# TamaCollar1_Mk1__V45.net
KiCad netlist of a schematic drawn in EAGLE
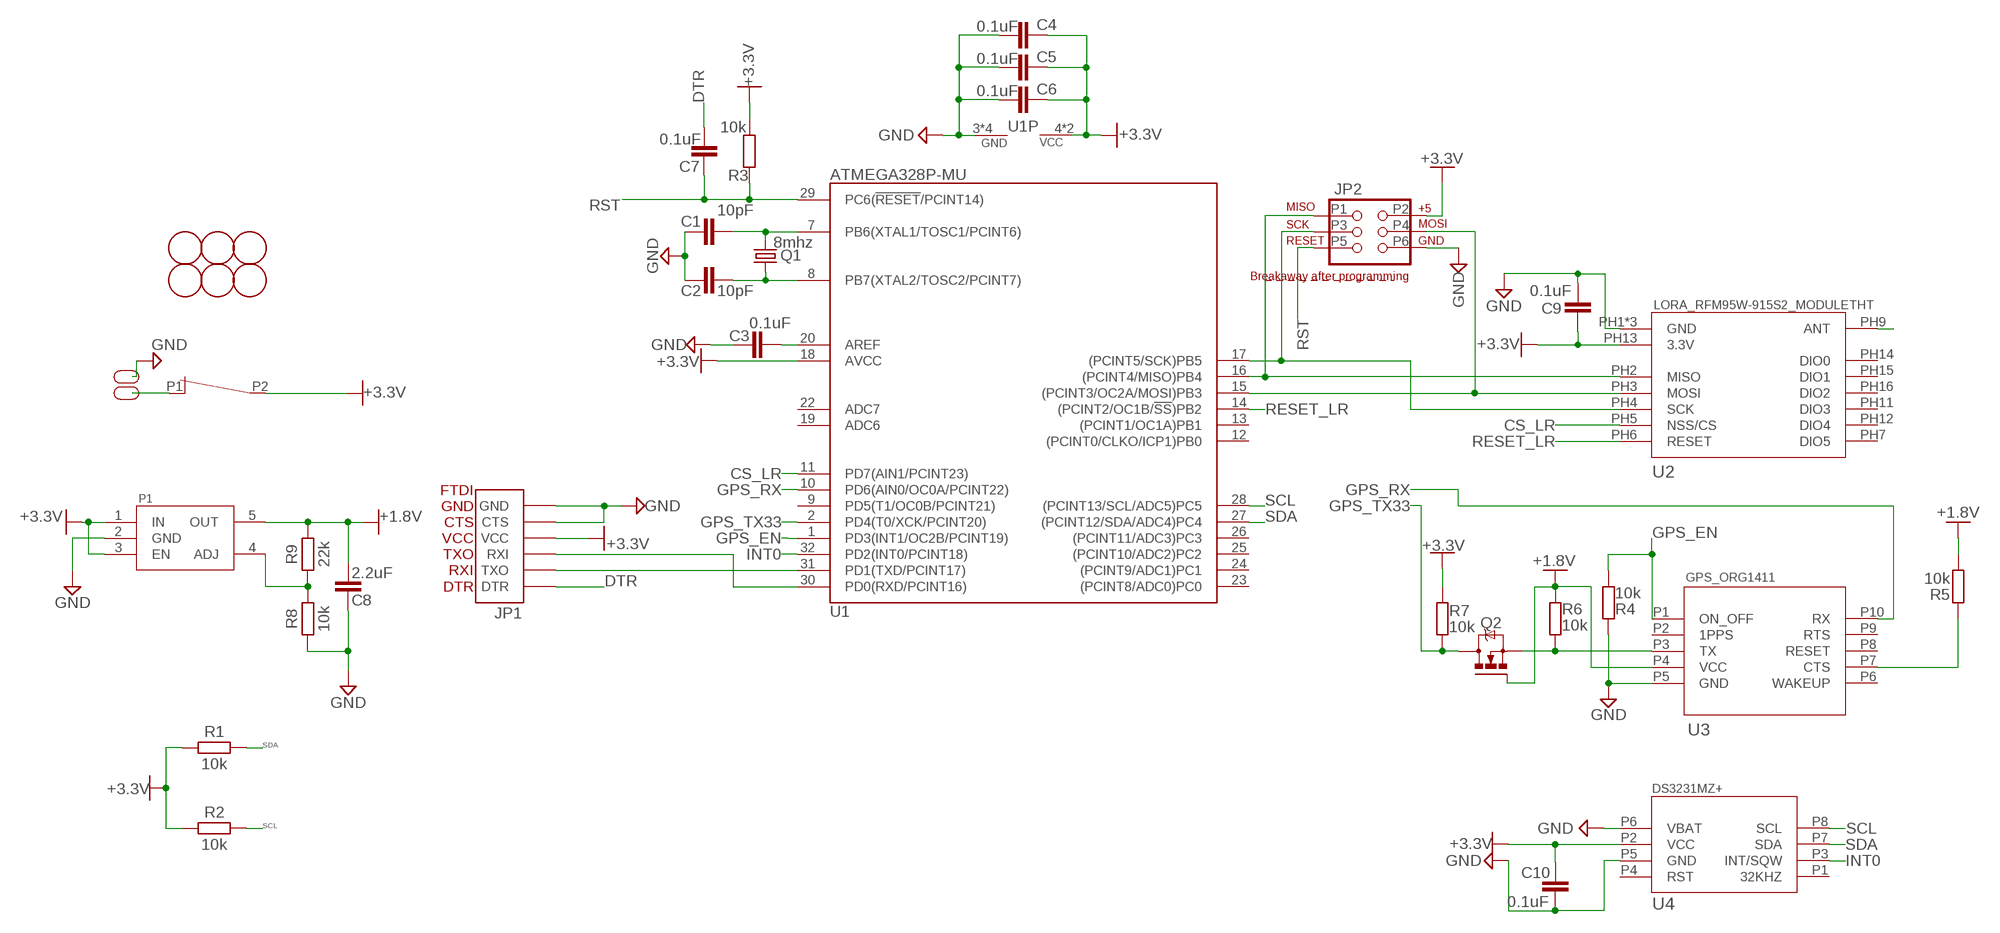
[diagram p0: schematic, sheet 1]

(export (version "E")
  (design (tool "Eeschema 10.0.6"))
  (components
    (comp (ref "BATT+")
      (value "BREAKOUT_PADL")
      (footprint "eagle-import:BREAKOUT_PAD_1_1X2MM")
      (libsource (lib "eagle-import") (part "BREAKOUT_PADL"))
    )
    (comp (ref "BR2")
      (value "MOUSEBITE3X1.25")
      (footprint "eagle-import:MOUSEBITE_3H_6TRACE(1.25MM)")
      (libsource (lib "eagle-import") (part "MOUSEBITE3X1.25"))
    )
    (comp (ref "C1")
      (value "10pF")
      (footprint "eagle-import:CAPC1005X60")
      (libsource (lib "eagle-import") (part "CCHIP-0402(1005-METRIC)_"))
    )
    (comp (ref "C2")
      (value "10pF")
      (footprint "eagle-import:CAPC1005X60")
      (libsource (lib "eagle-import") (part "CCHIP-0402(1005-METRIC)_"))
    )
    (comp (ref "C3")
      (value "0.1uF")
      (footprint "eagle-import:CAPC1005X60")
      (libsource (lib "eagle-import") (part "CCHIP-0402(1005-METRIC)_"))
    )
    (comp (ref "C4")
      (value "0.1uF")
      (footprint "eagle-import:CAPC1005X60")
      (libsource (lib "eagle-import") (part "CCHIP-0402(1005-METRIC)_"))
    )
    (comp (ref "C5")
      (value "0.1uF")
      (footprint "eagle-import:CAPC1005X60")
      (libsource (lib "eagle-import") (part "CCHIP-0402(1005-METRIC)_"))
    )
    (comp (ref "C6")
      (value "0.1uF")
      (footprint "eagle-import:CAPC1005X60")
      (libsource (lib "eagle-import") (part "CCHIP-0402(1005-METRIC)_"))
    )
    (comp (ref "C7")
      (value "0.1uF")
      (footprint "eagle-import:CAPC1005X60")
      (libsource (lib "eagle-import") (part "CCHIP-0402(1005-METRIC)_"))
    )
    (comp (ref "C8")
      (value "2.2uF")
      (footprint "eagle-import:CAPC1005X60")
      (libsource (lib "eagle-import") (part "CCHIP-0402(1005-METRIC)_"))
    )
    (comp (ref "C9")
      (value "0.1uF")
      (footprint "eagle-import:CAPC1005X60")
      (libsource (lib "eagle-import") (part "CCHIP-0402(1005-METRIC)_"))
    )
    (comp (ref "C10")
      (value "0.1uF")
      (footprint "eagle-import:CAPC1005X60")
      (libsource (lib "eagle-import") (part "CCHIP-0402(1005-METRIC)_"))
    )
    (comp (ref "F1")
      (value "FIDUCIAL")
      (footprint "eagle-import:FIDUCIAL_1MM")
      (libsource (lib "eagle-import") (part "FIDUCIAL"))
    )
    (comp (ref "F2")
      (value "FIDUCIAL")
      (footprint "eagle-import:FIDUCIAL_1MM")
      (libsource (lib "eagle-import") (part "FIDUCIAL"))
    )
    (comp (ref "F3")
      (value "FIDUCIAL")
      (footprint "eagle-import:FIDUCIAL_1MM")
      (libsource (lib "eagle-import") (part "FIDUCIAL"))
    )
    (comp (ref "F4")
      (value "FIDUCIAL")
      (footprint "eagle-import:FIDUCIAL_1MM")
      (libsource (lib "eagle-import") (part "FIDUCIAL"))
    )
    (comp (ref "F5")
      (value "FIDUCIAL")
      (footprint "eagle-import:FIDUCIAL_1MM")
      (libsource (lib "eagle-import") (part "FIDUCIAL"))
    )
    (comp (ref "F6")
      (value "FIDUCIAL")
      (footprint "eagle-import:FIDUCIAL_1MM")
      (libsource (lib "eagle-import") (part "FIDUCIAL"))
    )
    (comp (ref "GND")
      (value "BREAKOUT_PADL")
      (footprint "eagle-import:BREAKOUT_PAD_1_1X2MM")
      (libsource (lib "eagle-import") (part "BREAKOUT_PADL"))
    )
    (comp (ref "JP1")
      (value "FTDI_DEVICESMALL")
      (footprint "eagle-import:FTDI_DEVICE_SMD_SMALL")
      (libsource (lib "eagle-import") (part "FTDI_DEVICESMALL"))
    )
    (comp (ref "JP2")
      (value "AVR_SPI_PRG_61X6")
      (footprint "eagle-import:1X6-SMD")
      (libsource (lib "eagle-import") (part "AVR_SPI_PRG_61X6"))
    )
    (comp (ref "P1")
      (value "LDO_MIC5205YM5")
      (footprint "eagle-import:MIC5205")
      (libsource (lib "eagle-import") (part "LDO_MIC5205YM5"))
    )
    (comp (ref "Q1")
      (value "8mhz")
      (footprint "eagle-import:CRYSTAL_NX3225GD")
      (libsource (lib "eagle-import") (part "CRYSTAL"))
    )
    (comp (ref "Q2")
      (value "NMOSFET")
      (footprint "eagle-import:SOT23")
      (libsource (lib "eagle-import") (part "NMOSFETSOT23"))
    )
    (comp (ref "R1")
      (value "10k")
      (footprint "eagle-import:RESC1005X40")
      (libsource (lib "eagle-import") (part "RCHIP-0402(1005-METRIC)_"))
    )
    (comp (ref "R2")
      (value "10k")
      (footprint "eagle-import:RESC1005X40")
      (libsource (lib "eagle-import") (part "RCHIP-0402(1005-METRIC)_"))
    )
    (comp (ref "R3")
      (value "10k")
      (footprint "eagle-import:RESC1005X40")
      (libsource (lib "eagle-import") (part "RCHIP-0402(1005-METRIC)_"))
    )
    (comp (ref "R4")
      (value "10k")
      (footprint "eagle-import:RESC1005X40")
      (libsource (lib "eagle-import") (part "RCHIP-0402(1005-METRIC)_"))
    )
    (comp (ref "R5")
      (value "10k")
      (footprint "eagle-import:RESC1005X40")
      (libsource (lib "eagle-import") (part "RCHIP-0402(1005-METRIC)_"))
    )
    (comp (ref "R6")
      (value "10k")
      (footprint "eagle-import:RESC1005X40")
      (libsource (lib "eagle-import") (part "RCHIP-0402(1005-METRIC)_"))
    )
    (comp (ref "R7")
      (value "10k")
      (footprint "eagle-import:RESC1005X40")
      (libsource (lib "eagle-import") (part "RCHIP-0402(1005-METRIC)_"))
    )
    (comp (ref "R8")
      (value "10k")
      (footprint "eagle-import:RESC1005X40")
      (libsource (lib "eagle-import") (part "RCHIP-0402(1005-METRIC)_"))
    )
    (comp (ref "R9")
      (value "22k")
      (footprint "eagle-import:RESC1005X40")
      (libsource (lib "eagle-import") (part "RCHIP-0402(1005-METRIC)_"))
    )
    (comp (ref "SW1")
      (value "REED_SWITCH")
      (footprint "eagle-import:REED_CT05")
      (libsource (lib "eagle-import") (part "REED_SWITCH"))
    )
    (comp (ref "U1")
      (value "ATMEGA328P-MU")
      (footprint "eagle-import:QFN32_5X5_0.50")
      (fields
        (field (name "LINK") "https://www.rhydolabz.com/components-microcontrollers-c-172_192/atmega328pmu-smd-p-2612.html")
      )
      (libsource (lib "eagle-import") (part "ATMEGA8P-MU32"))
    )
    (comp (ref "U2")
      (value "LORA_RFM95W-915S2_MODULETHT")
      (footprint "eagle-import:LORA_RFM95W-915S2_16STANDOFFMODULE")
      (libsource (lib "eagle-import") (part "LORA_RFM95W-915S2_MODULETHT"))
    )
    (comp (ref "U3")
      (value "GPS_ORG1411")
      (footprint "eagle-import:ORG1411")
      (libsource (lib "eagle-import") (part "GPS_ORG1411"))
    )
    (comp (ref "U4")
      (value "DS3231MZ+")
      (footprint "eagle-import:DS3231MZ+_SOIC8")
      (libsource (lib "eagle-import") (part "DS3231MZ+"))
    )
  )
  (nets
    (net (code "1") (name "+1.8V") (class "Default")
      (node (ref "C8") (pin "2") (pinfunction "2_2") (pintype "passive"))
      (node (ref "P1") (pin "5") (pinfunction "OUT_5") (pintype "bidirectional"))
      (node (ref "Q2") (pin "1") (pinfunction "G_1") (pintype "passive"))
      (node (ref "R5") (pin "1") (pinfunction "1_1") (pintype "passive"))
      (node (ref "R6") (pin "2") (pinfunction "2_2") (pintype "passive"))
      (node (ref "R9") (pin "2") (pinfunction "2_2") (pintype "passive"))
      (node (ref "U3") (pin "P4") (pinfunction "VCC_P4") (pintype "power_in"))
    )
    (net (code "2") (name "+3.3V") (class "Default")
      (node (ref "C10") (pin "1") (pinfunction "1_1") (pintype "passive"))
      (node (ref "C4") (pin "1") (pinfunction "1_1") (pintype "passive"))
      (node (ref "C5") (pin "1") (pinfunction "1_1") (pintype "passive"))
      (node (ref "C6") (pin "1") (pinfunction "1_1") (pintype "passive"))
      (node (ref "C9") (pin "1") (pinfunction "1_1") (pintype "passive"))
      (node (ref "JP1") (pin "P4") (pinfunction "VCC_P4") (pintype "bidirectional"))
      (node (ref "JP2") (pin "P2") (pinfunction "2_P2") (pintype "passive"))
      (node (ref "P1") (pin "1") (pinfunction "IN_1") (pintype "bidirectional"))
      (node (ref "P1") (pin "3") (pinfunction "EN_3") (pintype "bidirectional"))
      (node (ref "R1") (pin "1") (pinfunction "1_1") (pintype "passive"))
      (node (ref "R2") (pin "1") (pinfunction "1_1") (pintype "passive"))
      (node (ref "R3") (pin "1") (pinfunction "1_1") (pintype "passive"))
      (node (ref "R7") (pin "2") (pinfunction "2_2") (pintype "passive"))
      (node (ref "SW1") (pin "P2") (pinfunction "PAD2_P2") (pintype "bidirectional"))
      (node (ref "U1") (pin "18") (pinfunction "AVCC_18") (pintype "power_in"))
      (node (ref "U1") (pin "4") (pinfunction "VCC_4") (pintype "power_in"))
      (node (ref "U1") (pin "6") (pinfunction "VCC_6") (pintype "power_in"))
      (node (ref "U2") (pin "PH13") (pinfunction "3.3V_PH13") (pintype "bidirectional"))
      (node (ref "U4") (pin "P2") (pinfunction "VCC_P2") (pintype "power_in"))
    )
    (net (code "3") (name "/CS_LR") (class "Default")
      (node (ref "U1") (pin "11") (pinfunction "PD7(AIN1/PCINT23)_11") (pintype "bidirectional"))
      (node (ref "U2") (pin "PH5") (pinfunction "NSS/CS_PH5") (pintype "bidirectional"))
    )
    (net (code "4") (name "/DTR") (class "Default")
      (node (ref "C7") (pin "2") (pinfunction "2_2") (pintype "passive"))
      (node (ref "JP1") (pin "P1") (pinfunction "DTR_P1") (pintype "bidirectional"))
    )
    (net (code "5") (name "/GPS_EN") (class "Default")
      (node (ref "R4") (pin "1") (pinfunction "1_1") (pintype "passive"))
      (node (ref "U1") (pin "1") (pinfunction "PD3(INT1/OC2B/PCINT19)_1") (pintype "bidirectional"))
      (node (ref "U3") (pin "P1") (pinfunction "ON_OFF_P1") (pintype "input"))
    )
    (net (code "6") (name "/GPS_RX") (class "Default")
      (node (ref "U1") (pin "10") (pinfunction "PD6(AIN0/OC0A/PCINT22)_10") (pintype "bidirectional"))
      (node (ref "U3") (pin "P10") (pinfunction "RX_P10") (pintype "bidirectional"))
    )
    (net (code "7") (name "/GPS_TX33") (class "Default")
      (node (ref "Q2") (pin "3") (pinfunction "D_3") (pintype "passive"))
      (node (ref "R7") (pin "1") (pinfunction "1_1") (pintype "passive"))
      (node (ref "U1") (pin "2") (pinfunction "PD4(T0/XCK/PCINT20)_2") (pintype "bidirectional"))
    )
    (net (code "8") (name "/INT0") (class "Default")
      (node (ref "U1") (pin "32") (pinfunction "PD2(INT0/PCINT18)_32") (pintype "bidirectional"))
      (node (ref "U4") (pin "P3") (pinfunction "INT/SQW_P3") (pintype "bidirectional"))
    )
    (net (code "9") (name "/RESET_LR") (class "Default")
      (node (ref "U1") (pin "14") (pinfunction "(PCINT2/OC1B/~{SS})PB2_14") (pintype "bidirectional"))
      (node (ref "U2") (pin "PH6") (pinfunction "RESET_PH6") (pintype "bidirectional"))
    )
    (net (code "10") (name "/RST") (class "Default")
      (node (ref "C7") (pin "1") (pinfunction "1_1") (pintype "passive"))
      (node (ref "JP2") (pin "P5") (pinfunction "5_P5") (pintype "passive"))
      (node (ref "R3") (pin "2") (pinfunction "2_2") (pintype "passive"))
      (node (ref "U1") (pin "29") (pinfunction "PC6(~{RESET}/PCINT14)_29") (pintype "bidirectional"))
    )
    (net (code "11") (name "/SCL") (class "Default")
      (node (ref "R2") (pin "2") (pinfunction "2_2") (pintype "passive"))
      (node (ref "U1") (pin "28") (pinfunction "(PCINT13/SCL/ADC5)PC5_28") (pintype "bidirectional"))
      (node (ref "U4") (pin "P8") (pinfunction "SCL_P8") (pintype "bidirectional"))
    )
    (net (code "12") (name "/SDA") (class "Default")
      (node (ref "R1") (pin "2") (pinfunction "2_2") (pintype "passive"))
      (node (ref "U1") (pin "27") (pinfunction "(PCINT12/SDA/ADC4)PC4_27") (pintype "bidirectional"))
      (node (ref "U4") (pin "P7") (pinfunction "SDA_P7") (pintype "bidirectional"))
    )
    (net (code "13") (name "GND") (class "Default")
      (node (ref "C1") (pin "1") (pinfunction "1_1") (pintype "passive"))
      (node (ref "C10") (pin "2") (pinfunction "2_2") (pintype "passive"))
      (node (ref "C2") (pin "1") (pinfunction "1_1") (pintype "passive"))
      (node (ref "C3") (pin "1") (pinfunction "1_1") (pintype "passive"))
      (node (ref "C4") (pin "2") (pinfunction "2_2") (pintype "passive"))
      (node (ref "C5") (pin "2") (pinfunction "2_2") (pintype "passive"))
      (node (ref "C6") (pin "2") (pinfunction "2_2") (pintype "passive"))
      (node (ref "C8") (pin "1") (pinfunction "1_1") (pintype "passive"))
      (node (ref "C9") (pin "2") (pinfunction "2_2") (pintype "passive"))
      (node (ref "GND") (pin "P$1") (pinfunction "P$1_P$1") (pintype "bidirectional"))
      (node (ref "JP1") (pin "P5") (pinfunction "CTS_P5") (pintype "bidirectional"))
      (node (ref "JP1") (pin "P6") (pinfunction "GND_P6") (pintype "bidirectional"))
      (node (ref "JP2") (pin "P6") (pinfunction "6_P6") (pintype "passive"))
      (node (ref "P1") (pin "2") (pinfunction "GND_2") (pintype "bidirectional"))
      (node (ref "R4") (pin "2") (pinfunction "2_2") (pintype "passive"))
      (node (ref "R8") (pin "1") (pinfunction "1_1") (pintype "passive"))
      (node (ref "U1") (pin "21") (pinfunction "GND_21") (pintype "power_in"))
      (node (ref "U1") (pin "3") (pinfunction "GND_3") (pintype "power_in"))
      (node (ref "U1") (pin "5") (pinfunction "GND_5") (pintype "power_in"))
      (node (ref "U1") (pin "EXP") (pinfunction "GND_EXP") (pintype "power_in"))
      (node (ref "U2") (pin "PH1") (pinfunction "GND_PH1") (pintype "bidirectional"))
      (node (ref "U2") (pin "PH10") (pinfunction "GND_PH10") (pintype "bidirectional"))
      (node (ref "U2") (pin "PH8") (pinfunction "GND_PH8") (pintype "bidirectional"))
      (node (ref "U3") (pin "P5") (pinfunction "GND_P5") (pintype "power_in"))
      (node (ref "U4") (pin "P5") (pinfunction "GND_P5") (pintype "power_in"))
      (node (ref "U4") (pin "P6") (pinfunction "VBAT_P6") (pintype "power_in"))
    )
    (net (code "14") (name "Net-(JP1-RXI)") (class "Default")
      (node (ref "JP1") (pin "P3") (pinfunction "RXI_P3") (pintype "bidirectional"))
      (node (ref "U1") (pin "30") (pinfunction "PD0(RXD/PCINT16)_30") (pintype "bidirectional"))
    )
    (net (code "15") (name "Net-(JP1-TXO)") (class "Default")
      (node (ref "JP1") (pin "P2") (pinfunction "TXO_P2") (pintype "bidirectional"))
      (node (ref "U1") (pin "31") (pinfunction "PD1(TXD/PCINT17)_31") (pintype "bidirectional"))
    )
    (net (code "16") (name "Net-(JP2-1)") (class "Default")
      (node (ref "JP2") (pin "P1") (pinfunction "1_P1") (pintype "passive"))
      (node (ref "U1") (pin "16") (pinfunction "(PCINT4/MISO)PB4_16") (pintype "bidirectional"))
      (node (ref "U2") (pin "PH2") (pinfunction "MISO_PH2") (pintype "bidirectional"))
    )
    (net (code "17") (name "Net-(JP2-3)") (class "Default")
      (node (ref "JP2") (pin "P3") (pinfunction "3_P3") (pintype "passive"))
      (node (ref "U1") (pin "17") (pinfunction "(PCINT5/SCK)PB5_17") (pintype "bidirectional"))
      (node (ref "U2") (pin "PH4") (pinfunction "SCK_PH4") (pintype "bidirectional"))
    )
    (net (code "18") (name "Net-(JP2-4)") (class "Default")
      (node (ref "JP2") (pin "P4") (pinfunction "4_P4") (pintype "passive"))
      (node (ref "U1") (pin "15") (pinfunction "(PCINT3/OC2A/MOSI)PB3_15") (pintype "bidirectional"))
      (node (ref "U2") (pin "PH3") (pinfunction "MOSI_PH3") (pintype "bidirectional"))
    )
    (net (code "19") (name "Net-(P1-ADJ)") (class "Default")
      (node (ref "P1") (pin "4") (pinfunction "ADJ_4") (pintype "bidirectional"))
      (node (ref "R8") (pin "2") (pinfunction "2_2") (pintype "passive"))
      (node (ref "R9") (pin "1") (pinfunction "1_1") (pintype "passive"))
    )
    (net (code "20") (name "Net-(Q1-1)") (class "Default")
      (node (ref "C2") (pin "2") (pinfunction "2_2") (pintype "passive"))
      (node (ref "Q1") (pin "P1") (pinfunction "1_P1") (pintype "passive"))
      (node (ref "U1") (pin "8") (pinfunction "PB7(XTAL2/TOSC2/PCINT7)_8") (pintype "bidirectional"))
    )
    (net (code "21") (name "Net-(Q1-2)") (class "Default")
      (node (ref "C1") (pin "2") (pinfunction "2_2") (pintype "passive"))
      (node (ref "Q1") (pin "P2") (pinfunction "2_P2") (pintype "passive"))
      (node (ref "U1") (pin "7") (pinfunction "PB6(XTAL1/TOSC1/PCINT6)_7") (pintype "bidirectional"))
    )
    (net (code "22") (name "Net-(Q2-S)") (class "Default")
      (node (ref "Q2") (pin "2") (pinfunction "S_2") (pintype "passive"))
      (node (ref "R6") (pin "1") (pinfunction "1_1") (pintype "passive"))
      (node (ref "U3") (pin "P3") (pinfunction "TX_P3") (pintype "bidirectional"))
    )
    (net (code "23") (name "Net-(SW1-PAD1)") (class "Default")
      (node (ref "BATT+") (pin "P$1") (pinfunction "P$1_P$1") (pintype "bidirectional"))
      (node (ref "SW1") (pin "P1") (pinfunction "PAD1_P1") (pintype "bidirectional"))
    )
    (net (code "24") (name "Net-(U1A-AREF)") (class "Default")
      (node (ref "C3") (pin "2") (pinfunction "2_2") (pintype "passive"))
      (node (ref "U1") (pin "20") (pinfunction "AREF_20") (pintype "passive"))
    )
    (net (code "25") (name "Net-(U3-CTS)") (class "Default")
      (node (ref "R5") (pin "2") (pinfunction "2_2") (pintype "passive"))
      (node (ref "U3") (pin "P7") (pinfunction "CTS_P7") (pintype "bidirectional"))
    )
    (net (code "26") (name "unconnected-(U1A-(PCINT0{slash}CLKO{slash}ICP1)PB0-Pad12)") (class "Default")
      (node (ref "U1") (pin "12") (pinfunction "(PCINT0/CLKO/ICP1)PB0_12") (pintype "bidirectional"))
    )
    (net (code "27") (name "unconnected-(U1A-(PCINT1{slash}OC1A)PB1-Pad13)") (class "Default")
      (node (ref "U1") (pin "13") (pinfunction "(PCINT1/OC1A)PB1_13") (pintype "bidirectional"))
    )
    (net (code "28") (name "unconnected-(U1A-(PCINT8{slash}ADC0)PC0-Pad23)") (class "Default")
      (node (ref "U1") (pin "23") (pinfunction "(PCINT8/ADC0)PC0_23") (pintype "bidirectional"))
    )
    (net (code "29") (name "unconnected-(U1A-(PCINT9{slash}ADC1)PC1-Pad24)") (class "Default")
      (node (ref "U1") (pin "24") (pinfunction "(PCINT9/ADC1)PC1_24") (pintype "bidirectional"))
    )
    (net (code "30") (name "unconnected-(U1A-(PCINT10{slash}ADC2)PC2-Pad25)") (class "Default")
      (node (ref "U1") (pin "25") (pinfunction "(PCINT10/ADC2)PC2_25") (pintype "bidirectional"))
    )
    (net (code "31") (name "unconnected-(U1A-(PCINT11{slash}ADC3)PC3-Pad26)") (class "Default")
      (node (ref "U1") (pin "26") (pinfunction "(PCINT11/ADC3)PC3_26") (pintype "bidirectional"))
    )
    (net (code "32") (name "unconnected-(U1A-ADC6-Pad19)") (class "Default")
      (node (ref "U1") (pin "19") (pinfunction "ADC6_19") (pintype "bidirectional"))
    )
    (net (code "33") (name "unconnected-(U1A-ADC7-Pad22)") (class "Default")
      (node (ref "U1") (pin "22") (pinfunction "ADC7_22") (pintype "bidirectional"))
    )
    (net (code "34") (name "unconnected-(U1A-PD5(T1{slash}OC0B{slash}PCINT21)-Pad9)") (class "Default")
      (node (ref "U1") (pin "9") (pinfunction "PD5(T1/OC0B/PCINT21)_9") (pintype "bidirectional"))
    )
    (net (code "35") (name "unconnected-(U2-ANT-PadPH9)") (class "Default")
      (node (ref "U2") (pin "PH9") (pinfunction "ANT_PH9") (pintype "bidirectional"))
    )
    (net (code "36") (name "unconnected-(U2-DIO0-PadPH14)") (class "Default")
      (node (ref "U2") (pin "PH14") (pinfunction "DIO0_PH14") (pintype "bidirectional"))
    )
    (net (code "37") (name "unconnected-(U2-DIO1-PadPH15)") (class "Default")
      (node (ref "U2") (pin "PH15") (pinfunction "DIO1_PH15") (pintype "bidirectional"))
    )
    (net (code "38") (name "unconnected-(U2-DIO2-PadPH16)") (class "Default")
      (node (ref "U2") (pin "PH16") (pinfunction "DIO2_PH16") (pintype "bidirectional"))
    )
    (net (code "39") (name "unconnected-(U2-DIO3-PadPH11)") (class "Default")
      (node (ref "U2") (pin "PH11") (pinfunction "DIO3_PH11") (pintype "bidirectional"))
    )
    (net (code "40") (name "unconnected-(U2-DIO4-PadPH12)") (class "Default")
      (node (ref "U2") (pin "PH12") (pinfunction "DIO4_PH12") (pintype "bidirectional"))
    )
    (net (code "41") (name "unconnected-(U2-DIO5-PadPH7)") (class "Default")
      (node (ref "U2") (pin "PH7") (pinfunction "DIO5_PH7") (pintype "bidirectional"))
    )
    (net (code "42") (name "unconnected-(U3-1PPS-PadP2)") (class "Default")
      (node (ref "U3") (pin "P2") (pinfunction "1PPS_P2") (pintype "output"))
    )
    (net (code "43") (name "unconnected-(U3-RESET-PadP8)") (class "Default")
      (node (ref "U3") (pin "P8") (pinfunction "RESET_P8") (pintype "input"))
    )
    (net (code "44") (name "unconnected-(U3-RTS-PadP9)") (class "Default")
      (node (ref "U3") (pin "P9") (pinfunction "RTS_P9") (pintype "bidirectional"))
    )
    (net (code "45") (name "unconnected-(U3-WAKEUP-PadP6)") (class "Default")
      (node (ref "U3") (pin "P6") (pinfunction "WAKEUP_P6") (pintype "output"))
    )
    (net (code "46") (name "unconnected-(U4-32KHZ-PadP1)") (class "Default")
      (node (ref "U4") (pin "P1") (pinfunction "32KHZ_P1") (pintype "bidirectional"))
    )
    (net (code "47") (name "unconnected-(U4-RST-PadP4)") (class "Default")
      (node (ref "U4") (pin "P4") (pinfunction "RST_P4") (pintype "bidirectional"))
    )
  )
)
